# Viisilukk.net
KiCad netlist of a schematic drawn in EAGLE
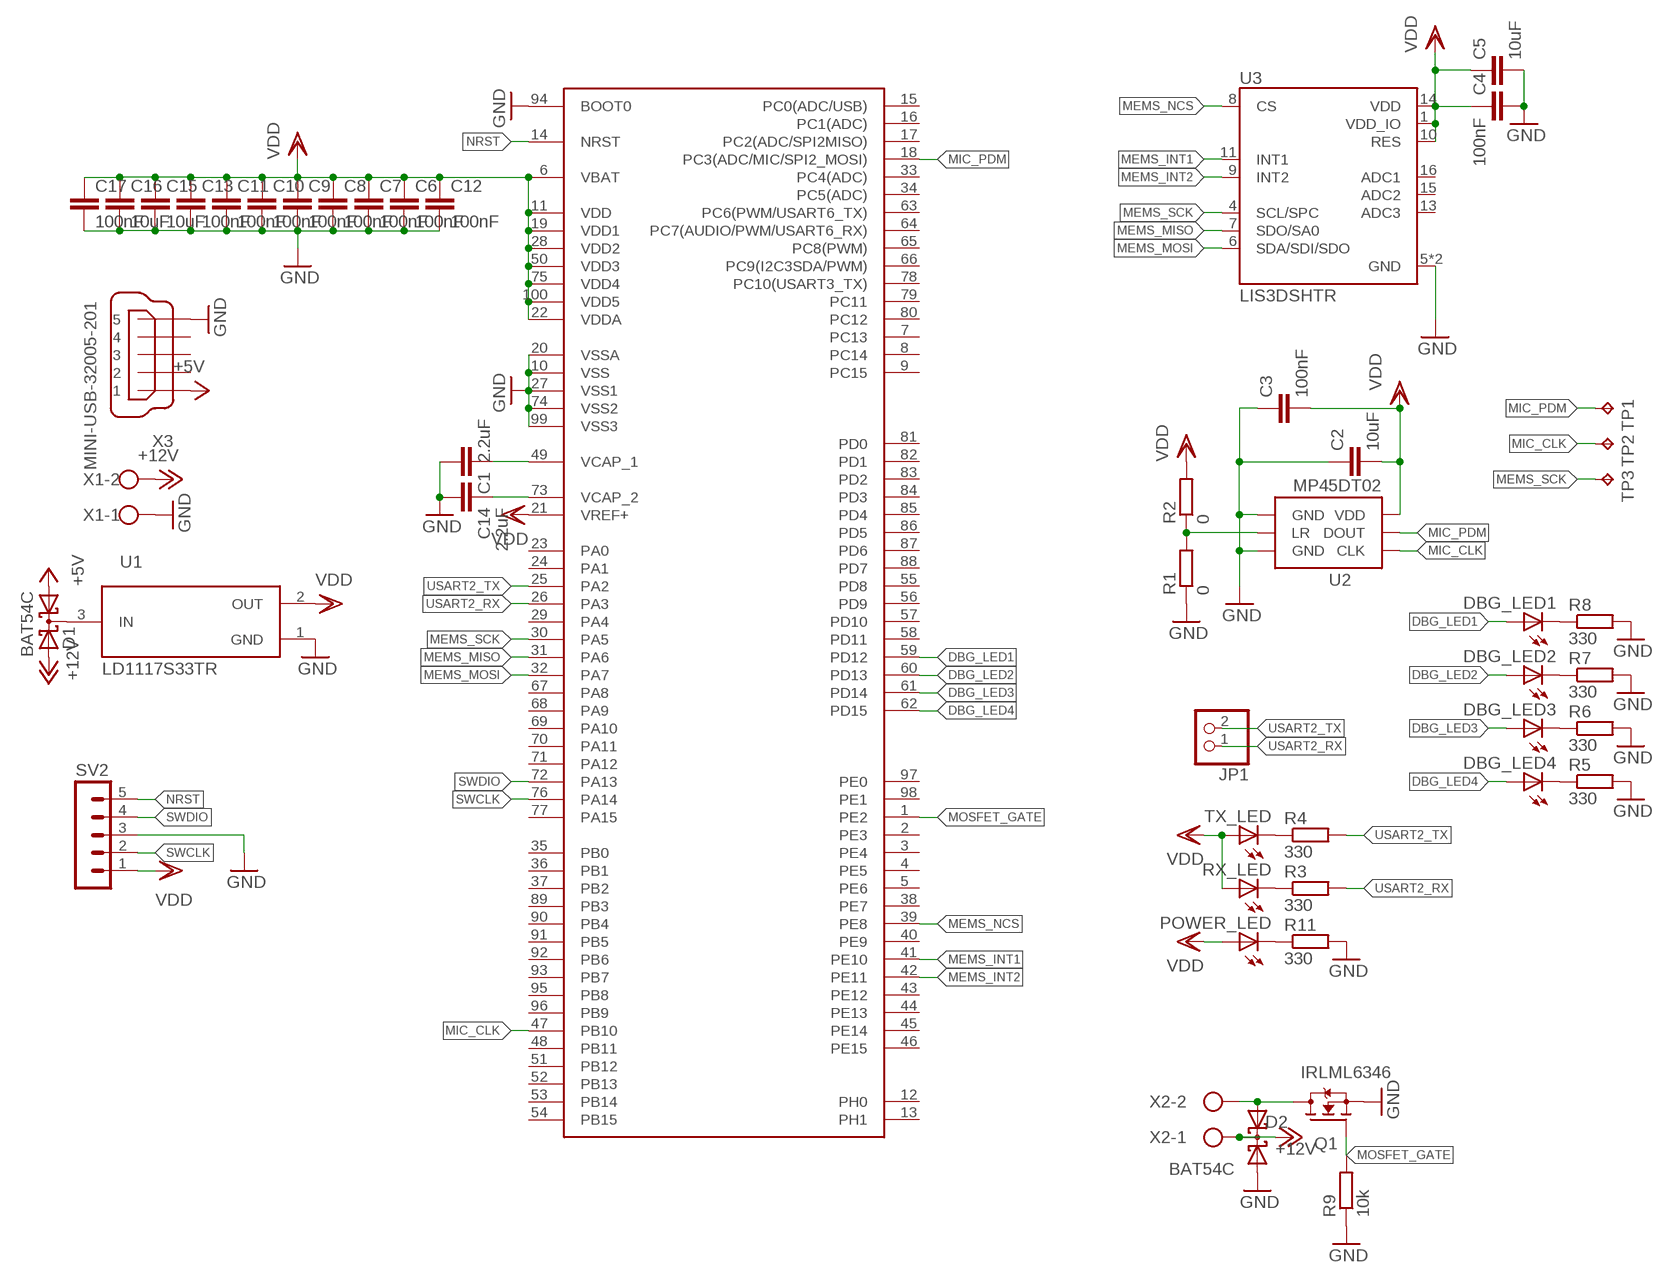
[diagram p0: schematic, sheet 1]

(export (version "E")
  (design (tool "Eeschema 10.0.6"))
  (components
    (comp (ref "C1")
      (value "2.2uF")
      (footprint "eagle-import:C0603")
      (libsource (lib "eagle-import") (part "C-EUC0603"))
    )
    (comp (ref "C2")
      (value "10uF")
      (footprint "eagle-import:C0805")
      (libsource (lib "eagle-import") (part "C-EUC0805"))
    )
    (comp (ref "C3")
      (value "100nF")
      (footprint "eagle-import:C0603")
      (libsource (lib "eagle-import") (part "C-EUC0603"))
    )
    (comp (ref "C4")
      (value "100nF")
      (footprint "eagle-import:C0603")
      (libsource (lib "eagle-import") (part "C-EUC0603"))
    )
    (comp (ref "C5")
      (value "10uF")
      (footprint "eagle-import:C0805")
      (libsource (lib "eagle-import") (part "C-EUC0805"))
    )
    (comp (ref "C6")
      (value "100nF")
      (footprint "eagle-import:C0603")
      (libsource (lib "eagle-import") (part "C-EUC0603"))
    )
    (comp (ref "C7")
      (value "100nF")
      (footprint "eagle-import:C0603")
      (libsource (lib "eagle-import") (part "C-EUC0603"))
    )
    (comp (ref "C8")
      (value "100nF")
      (footprint "eagle-import:C0603")
      (libsource (lib "eagle-import") (part "C-EUC0603"))
    )
    (comp (ref "C9")
      (value "100nF")
      (footprint "eagle-import:C0603")
      (libsource (lib "eagle-import") (part "C-EUC0603"))
    )
    (comp (ref "C10")
      (value "100nF")
      (footprint "eagle-import:C0603")
      (libsource (lib "eagle-import") (part "C-EUC0603"))
    )
    (comp (ref "C11")
      (value "100nF")
      (footprint "eagle-import:C0603")
      (libsource (lib "eagle-import") (part "C-EUC0603"))
    )
    (comp (ref "C12")
      (value "100nF")
      (footprint "eagle-import:C0603")
      (libsource (lib "eagle-import") (part "C-EUC0603"))
    )
    (comp (ref "C13")
      (value "100nF")
      (footprint "eagle-import:C0603")
      (libsource (lib "eagle-import") (part "C-EUC0603"))
    )
    (comp (ref "C14")
      (value "2.2uF")
      (footprint "eagle-import:C0603")
      (libsource (lib "eagle-import") (part "C-EUC0603"))
    )
    (comp (ref "C15")
      (value "10uF")
      (footprint "eagle-import:C0805")
      (libsource (lib "eagle-import") (part "C-EUC0805"))
    )
    (comp (ref "C16")
      (value "10uF")
      (footprint "eagle-import:C0805")
      (libsource (lib "eagle-import") (part "C-EUC0805"))
    )
    (comp (ref "C17")
      (value "100nF")
      (footprint "eagle-import:C0603")
      (libsource (lib "eagle-import") (part "C-EUC0603"))
    )
    (comp (ref "D1")
      (value "BAT54C")
      (footprint "eagle-import:SOT23")
      (libsource (lib "eagle-import") (part "BAT54C"))
    )
    (comp (ref "D2")
      (value "BAT54C")
      (footprint "eagle-import:SOT23")
      (libsource (lib "eagle-import") (part "BAT54C"))
    )
    (comp (ref "DBG_LED1")
      (value "LEDCHIP-LED0603")
      (footprint "eagle-import:CHIP-LED0603")
      (libsource (lib "eagle-import") (part "LEDCHIP-LED0603"))
    )
    (comp (ref "DBG_LED2")
      (value "LEDCHIP-LED0603")
      (footprint "eagle-import:CHIP-LED0603")
      (libsource (lib "eagle-import") (part "LEDCHIP-LED0603"))
    )
    (comp (ref "DBG_LED3")
      (value "LEDCHIP-LED0603")
      (footprint "eagle-import:CHIP-LED0603")
      (libsource (lib "eagle-import") (part "LEDCHIP-LED0603"))
    )
    (comp (ref "DBG_LED4")
      (value "LEDCHIP-LED0603")
      (footprint "eagle-import:CHIP-LED0603")
      (libsource (lib "eagle-import") (part "LEDCHIP-LED0603"))
    )
    (comp (ref "JP1")
      (value "PINHD-1X2")
      (footprint "eagle-import:1X02")
      (libsource (lib "eagle-import") (part "PINHD-1X2"))
    )
    (comp (ref "POWER_LED")
      (value "LEDCHIP-LED0603")
      (footprint "eagle-import:CHIP-LED0603")
      (libsource (lib "eagle-import") (part "LEDCHIP-LED0603"))
    )
    (comp (ref "Q1")
      (value "IRLML6346")
      (footprint "eagle-import:SOT23")
      (fields (field (name "MF") "Fairchild") (field (name "MPN") "BSS138"))
      (libsource (lib "eagle-import") (part "IRLML6346"))
    )
    (comp (ref "R1")
      (value "0")
      (footprint "eagle-import:R0603")
      (libsource (lib "eagle-import") (part "R-EU_R0603"))
    )
    (comp (ref "R2")
      (value "0")
      (footprint "eagle-import:R0603")
      (libsource (lib "eagle-import") (part "R-EU_R0603"))
    )
    (comp (ref "R3")
      (value "330")
      (footprint "eagle-import:R0603")
      (libsource (lib "eagle-import") (part "R-EU_R0603"))
    )
    (comp (ref "R4")
      (value "330")
      (footprint "eagle-import:R0603")
      (libsource (lib "eagle-import") (part "R-EU_R0603"))
    )
    (comp (ref "R5")
      (value "330")
      (footprint "eagle-import:R0603")
      (libsource (lib "eagle-import") (part "R-EU_R0603"))
    )
    (comp (ref "R6")
      (value "330")
      (footprint "eagle-import:R0603")
      (libsource (lib "eagle-import") (part "R-EU_R0603"))
    )
    (comp (ref "R7")
      (value "330")
      (footprint "eagle-import:R0603")
      (libsource (lib "eagle-import") (part "R-EU_R0603"))
    )
    (comp (ref "R8")
      (value "330")
      (footprint "eagle-import:R0603")
      (libsource (lib "eagle-import") (part "R-EU_R0603"))
    )
    (comp (ref "R9")
      (value "10k")
      (footprint "eagle-import:R0603")
      (libsource (lib "eagle-import") (part "R-EU_R0603"))
    )
    (comp (ref "R11")
      (value "330")
      (footprint "eagle-import:R0603")
      (libsource (lib "eagle-import") (part "R-EU_R0603"))
    )
    (comp (ref "RX_LED")
      (value "LEDCHIP-LED0603")
      (footprint "eagle-import:CHIP-LED0603")
      (libsource (lib "eagle-import") (part "LEDCHIP-LED0603"))
    )
    (comp (ref "SV2")
      (value "MA05-1")
      (footprint "eagle-import:MA05-1")
      (libsource (lib "eagle-import") (part "MA05-1"))
    )
    (comp (ref "TP1")
      (value "TPB2,54")
      (footprint "eagle-import:B2,54")
      (libsource (lib "eagle-import") (part "TPB2,54"))
    )
    (comp (ref "TP2")
      (value "TPB2,54")
      (footprint "eagle-import:B2,54")
      (libsource (lib "eagle-import") (part "TPB2,54"))
    )
    (comp (ref "TP3")
      (value "TPB2,54")
      (footprint "eagle-import:B2,54")
      (libsource (lib "eagle-import") (part "TPB2,54"))
    )
    (comp (ref "TX_LED")
      (value "LEDCHIP-LED0603")
      (footprint "eagle-import:CHIP-LED0603")
      (libsource (lib "eagle-import") (part "LEDCHIP-LED0603"))
    )
    (comp (ref "U$1")
      (value "STM32F407STM32D40X")
      (footprint "eagle-import:LQFP100")
      (libsource (lib "eagle-import") (part "STM32F407STM32D40X"))
    )
    (comp (ref "U1")
      (value "LD1117S33TR")
      (footprint "eagle-import:SOT230P700X180-4N")
      (fields (field (name "MF") "STMicroelectronics"))
      (libsource (lib "eagle-import") (part "LD1117S33TR"))
    )
    (comp (ref "U2")
      (value "MP45DT02")
      (footprint "eagle-import:ST_HLGA6")
      (fields (field (name "MF") "STMicroelectronics"))
      (libsource (lib "eagle-import") (part "MP45DT02"))
    )
    (comp (ref "U3")
      (value "LIS3DSHTR")
      (footprint "eagle-import:LGA16R50P5X3_300X300X100N")
      (fields (field (name "MF") "STMicroelectronics"))
      (libsource (lib "eagle-import") (part "LIS3DSHTR"))
    )
    (comp (ref "X1")
      (value "W237-102")
      (footprint "eagle-import:W237-102")
      (fields (field (name "MPN") "237-102"))
      (libsource (lib "eagle-import") (part "W237-102"))
    )
    (comp (ref "X2")
      (value "W237-102")
      (footprint "eagle-import:W237-102")
      (fields (field (name "MPN") "237-102"))
      (libsource (lib "eagle-import") (part "W237-102"))
    )
    (comp (ref "X3")
      (value "MINI-USB-32005-201")
      (footprint "eagle-import:32005-201")
      (libsource (lib "eagle-import") (part "MINI-USB-32005-201"))
    )
  )
  (nets
    (net (code "1") (name "+5V") (class "Default")
      (node (ref "D1") (pin "1") (pinfunction "A1_1") (pintype "passive"))
      (node (ref "X3") (pin "1") (pinfunction "1_1") (pintype "passive"))
    )
    (net (code "2") (name "+12V") (class "Default")
      (node (ref "D1") (pin "2") (pinfunction "A2_2") (pintype "passive"))
      (node (ref "D2") (pin "3") (pinfunction "CC_3") (pintype "passive"))
      (node (ref "X1") (pin "2") (pinfunction "KL_2") (pintype "passive"))
      (node (ref "X2") (pin "1") (pinfunction "KL_1") (pintype "passive"))
    )
    (net (code "3") (name "DBG_LED1") (class "Default")
      (node (ref "DBG_LED1") (pin "A") (pinfunction "A_A") (pintype "passive"))
      (node (ref "U$1") (pin "59") (pinfunction "PD12_59") (pintype "bidirectional"))
    )
    (net (code "4") (name "DBG_LED2") (class "Default")
      (node (ref "DBG_LED2") (pin "A") (pinfunction "A_A") (pintype "passive"))
      (node (ref "U$1") (pin "60") (pinfunction "PD13_60") (pintype "bidirectional"))
    )
    (net (code "5") (name "DBG_LED3") (class "Default")
      (node (ref "DBG_LED3") (pin "A") (pinfunction "A_A") (pintype "passive"))
      (node (ref "U$1") (pin "61") (pinfunction "PD14_61") (pintype "bidirectional"))
    )
    (net (code "6") (name "DBG_LED4") (class "Default")
      (node (ref "DBG_LED4") (pin "A") (pinfunction "A_A") (pintype "passive"))
      (node (ref "U$1") (pin "62") (pinfunction "PD15_62") (pintype "bidirectional"))
    )
    (net (code "7") (name "GND") (class "Default")
      (node (ref "C1") (pin "2") (pinfunction "2_2") (pintype "passive"))
      (node (ref "C10") (pin "2") (pinfunction "2_2") (pintype "passive"))
      (node (ref "C11") (pin "2") (pinfunction "2_2") (pintype "passive"))
      (node (ref "C12") (pin "2") (pinfunction "2_2") (pintype "passive"))
      (node (ref "C13") (pin "2") (pinfunction "2_2") (pintype "passive"))
      (node (ref "C14") (pin "2") (pinfunction "2_2") (pintype "passive"))
      (node (ref "C15") (pin "2") (pinfunction "2_2") (pintype "passive"))
      (node (ref "C16") (pin "2") (pinfunction "2_2") (pintype "passive"))
      (node (ref "C17") (pin "2") (pinfunction "2_2") (pintype "passive"))
      (node (ref "C2") (pin "1") (pinfunction "1_1") (pintype "passive"))
      (node (ref "C3") (pin "1") (pinfunction "1_1") (pintype "passive"))
      (node (ref "C4") (pin "2") (pinfunction "2_2") (pintype "passive"))
      (node (ref "C5") (pin "2") (pinfunction "2_2") (pintype "passive"))
      (node (ref "C6") (pin "2") (pinfunction "2_2") (pintype "passive"))
      (node (ref "C7") (pin "2") (pinfunction "2_2") (pintype "passive"))
      (node (ref "C8") (pin "2") (pinfunction "2_2") (pintype "passive"))
      (node (ref "C9") (pin "2") (pinfunction "2_2") (pintype "passive"))
      (node (ref "D2") (pin "1") (pinfunction "A1_1") (pintype "passive"))
      (node (ref "Q1") (pin "2") (pinfunction "S_2") (pintype "passive"))
      (node (ref "R1") (pin "1") (pinfunction "1_1") (pintype "passive"))
      (node (ref "R11") (pin "2") (pinfunction "2_2") (pintype "passive"))
      (node (ref "R5") (pin "2") (pinfunction "2_2") (pintype "passive"))
      (node (ref "R6") (pin "2") (pinfunction "2_2") (pintype "passive"))
      (node (ref "R7") (pin "2") (pinfunction "2_2") (pintype "passive"))
      (node (ref "R8") (pin "2") (pinfunction "2_2") (pintype "passive"))
      (node (ref "R9") (pin "1") (pinfunction "1_1") (pintype "passive"))
      (node (ref "SV2") (pin "3") (pinfunction "3_3") (pintype "passive"))
      (node (ref "U$1") (pin "10") (pinfunction "VSS_10") (pintype "bidirectional"))
      (node (ref "U$1") (pin "20") (pinfunction "VSSA_20") (pintype "bidirectional"))
      (node (ref "U$1") (pin "27") (pinfunction "VSS1_27") (pintype "bidirectional"))
      (node (ref "U$1") (pin "74") (pinfunction "VSS2_74") (pintype "bidirectional"))
      (node (ref "U$1") (pin "94") (pinfunction "BOOT0_94") (pintype "bidirectional"))
      (node (ref "U$1") (pin "99") (pinfunction "VSS3_99") (pintype "bidirectional"))
      (node (ref "U1") (pin "1") (pinfunction "GND_1") (pintype "power_in"))
      (node (ref "U2") (pin "1") (pinfunction "GND_1") (pintype "bidirectional"))
      (node (ref "U2") (pin "3") (pinfunction "GND_3") (pintype "bidirectional"))
      (node (ref "U3") (pin "12") (pinfunction "GND_12") (pintype "power_in"))
      (node (ref "U3") (pin "5") (pinfunction "GND_5") (pintype "power_in"))
      (node (ref "X1") (pin "1") (pinfunction "KL_1") (pintype "passive"))
      (node (ref "X3") (pin "5") (pinfunction "5_5") (pintype "passive"))
    )
    (net (code "8") (name "MEMS_INT1") (class "Default")
      (node (ref "U$1") (pin "41") (pinfunction "PE10_41") (pintype "bidirectional"))
      (node (ref "U3") (pin "11") (pinfunction "INT1_11") (pintype "input"))
    )
    (net (code "9") (name "MEMS_INT2") (class "Default")
      (node (ref "U$1") (pin "42") (pinfunction "PE11_42") (pintype "bidirectional"))
      (node (ref "U3") (pin "9") (pinfunction "INT2_9") (pintype "input"))
    )
    (net (code "10") (name "MEMS_MISO") (class "Default")
      (node (ref "U$1") (pin "31") (pinfunction "PA6_31") (pintype "bidirectional"))
      (node (ref "U3") (pin "7") (pinfunction "SDO/SA0_7") (pintype "output"))
    )
    (net (code "11") (name "MEMS_MOSI") (class "Default")
      (node (ref "U$1") (pin "32") (pinfunction "PA7_32") (pintype "bidirectional"))
      (node (ref "U3") (pin "6") (pinfunction "SDA/SDI/SDO_6") (pintype "bidirectional"))
    )
    (net (code "12") (name "MEMS_NCS") (class "Default")
      (node (ref "U$1") (pin "39") (pinfunction "PE8_39") (pintype "bidirectional"))
      (node (ref "U3") (pin "8") (pinfunction "CS_8") (pintype "input"))
    )
    (net (code "13") (name "MEMS_SCK") (class "Default")
      (node (ref "TP3") (pin "TP") (pinfunction "TP_TP") (pintype "input"))
      (node (ref "U$1") (pin "30") (pinfunction "PA5_30") (pintype "bidirectional"))
      (node (ref "U3") (pin "4") (pinfunction "SCL/SPC_4") (pintype "input"))
    )
    (net (code "14") (name "MIC_CLK") (class "Default")
      (node (ref "TP2") (pin "TP") (pinfunction "TP_TP") (pintype "input"))
      (node (ref "U$1") (pin "47") (pinfunction "PB10_47") (pintype "bidirectional"))
      (node (ref "U2") (pin "4") (pinfunction "CLK_4") (pintype "bidirectional"))
    )
    (net (code "15") (name "MIC_PDM") (class "Default")
      (node (ref "TP1") (pin "TP") (pinfunction "TP_TP") (pintype "input"))
      (node (ref "U$1") (pin "18") (pinfunction "PC3(ADC/MIC/SPI2_MOSI)_18") (pintype "bidirectional"))
      (node (ref "U2") (pin "5") (pinfunction "DOUT_5") (pintype "bidirectional"))
    )
    (net (code "16") (name "MOSFET_GATE") (class "Default")
      (node (ref "Q1") (pin "1") (pinfunction "G_1") (pintype "passive"))
      (node (ref "R9") (pin "2") (pinfunction "2_2") (pintype "passive"))
      (node (ref "U$1") (pin "1") (pinfunction "PE2_1") (pintype "bidirectional"))
    )
    (net (code "17") (name "NRST") (class "Default")
      (node (ref "SV2") (pin "5") (pinfunction "5_5") (pintype "passive"))
      (node (ref "U$1") (pin "14") (pinfunction "NRST_14") (pintype "bidirectional"))
    )
    (net (code "18") (name "Net-(D1-CC)") (class "Default")
      (node (ref "D1") (pin "3") (pinfunction "CC_3") (pintype "passive"))
      (node (ref "U1") (pin "3") (pinfunction "IN_3") (pintype "input"))
    )
    (net (code "19") (name "Net-(D2-A2)") (class "Default")
      (node (ref "D2") (pin "2") (pinfunction "A2_2") (pintype "passive"))
      (node (ref "Q1") (pin "3") (pinfunction "D_3") (pintype "passive"))
      (node (ref "X2") (pin "2") (pinfunction "KL_2") (pintype "passive"))
    )
    (net (code "20") (name "Net-(DBG_LED1-PadC)") (class "Default")
      (node (ref "DBG_LED1") (pin "C") (pinfunction "C_C") (pintype "passive"))
      (node (ref "R8") (pin "1") (pinfunction "1_1") (pintype "passive"))
    )
    (net (code "21") (name "Net-(DBG_LED2-PadC)") (class "Default")
      (node (ref "DBG_LED2") (pin "C") (pinfunction "C_C") (pintype "passive"))
      (node (ref "R7") (pin "1") (pinfunction "1_1") (pintype "passive"))
    )
    (net (code "22") (name "Net-(DBG_LED3-PadC)") (class "Default")
      (node (ref "DBG_LED3") (pin "C") (pinfunction "C_C") (pintype "passive"))
      (node (ref "R6") (pin "1") (pinfunction "1_1") (pintype "passive"))
    )
    (net (code "23") (name "Net-(DBG_LED4-PadC)") (class "Default")
      (node (ref "DBG_LED4") (pin "C") (pinfunction "C_C") (pintype "passive"))
      (node (ref "R5") (pin "1") (pinfunction "1_1") (pintype "passive"))
    )
    (net (code "24") (name "Net-(POWER_LED-PadC)") (class "Default")
      (node (ref "POWER_LED") (pin "C") (pinfunction "C_C") (pintype "passive"))
      (node (ref "R11") (pin "1") (pinfunction "1_1") (pintype "passive"))
    )
    (net (code "25") (name "Net-(R3-Pad1)") (class "Default")
      (node (ref "R3") (pin "1") (pinfunction "1_1") (pintype "passive"))
      (node (ref "RX_LED") (pin "C") (pinfunction "C_C") (pintype "passive"))
    )
    (net (code "26") (name "Net-(R4-Pad1)") (class "Default")
      (node (ref "R4") (pin "1") (pinfunction "1_1") (pintype "passive"))
      (node (ref "TX_LED") (pin "C") (pinfunction "C_C") (pintype "passive"))
    )
    (net (code "27") (name "Net-(U$1-VCAP_1)") (class "Default")
      (node (ref "C1") (pin "1") (pinfunction "1_1") (pintype "passive"))
      (node (ref "U$1") (pin "49") (pinfunction "VCAP_1_49") (pintype "bidirectional"))
    )
    (net (code "28") (name "Net-(U$1-VCAP_2)") (class "Default")
      (node (ref "C14") (pin "1") (pinfunction "1_1") (pintype "passive"))
      (node (ref "U$1") (pin "73") (pinfunction "VCAP_2_73") (pintype "bidirectional"))
    )
    (net (code "29") (name "Net-(U2-LR)") (class "Default")
      (node (ref "R1") (pin "2") (pinfunction "2_2") (pintype "passive"))
      (node (ref "R2") (pin "1") (pinfunction "1_1") (pintype "passive"))
      (node (ref "U2") (pin "2") (pinfunction "LR_2") (pintype "bidirectional"))
    )
    (net (code "30") (name "SWCLK") (class "Default")
      (node (ref "SV2") (pin "2") (pinfunction "2_2") (pintype "passive"))
      (node (ref "U$1") (pin "76") (pinfunction "PA14_76") (pintype "bidirectional"))
    )
    (net (code "31") (name "SWDIO") (class "Default")
      (node (ref "SV2") (pin "4") (pinfunction "4_4") (pintype "passive"))
      (node (ref "U$1") (pin "72") (pinfunction "PA13_72") (pintype "bidirectional"))
    )
    (net (code "32") (name "USART2_RX") (class "Default")
      (node (ref "JP1") (pin "1") (pinfunction "1_1") (pintype "passive"))
      (node (ref "R3") (pin "2") (pinfunction "2_2") (pintype "passive"))
      (node (ref "U$1") (pin "26") (pinfunction "PA3_26") (pintype "bidirectional"))
    )
    (net (code "33") (name "USART2_TX") (class "Default")
      (node (ref "JP1") (pin "2") (pinfunction "2_2") (pintype "passive"))
      (node (ref "R4") (pin "2") (pinfunction "2_2") (pintype "passive"))
      (node (ref "U$1") (pin "25") (pinfunction "PA2_25") (pintype "bidirectional"))
    )
    (net (code "34") (name "VDD") (class "Default")
      (node (ref "C10") (pin "1") (pinfunction "1_1") (pintype "passive"))
      (node (ref "C11") (pin "1") (pinfunction "1_1") (pintype "passive"))
      (node (ref "C12") (pin "1") (pinfunction "1_1") (pintype "passive"))
      (node (ref "C13") (pin "1") (pinfunction "1_1") (pintype "passive"))
      (node (ref "C15") (pin "1") (pinfunction "1_1") (pintype "passive"))
      (node (ref "C16") (pin "1") (pinfunction "1_1") (pintype "passive"))
      (node (ref "C17") (pin "1") (pinfunction "1_1") (pintype "passive"))
      (node (ref "C2") (pin "2") (pinfunction "2_2") (pintype "passive"))
      (node (ref "C3") (pin "2") (pinfunction "2_2") (pintype "passive"))
      (node (ref "C4") (pin "1") (pinfunction "1_1") (pintype "passive"))
      (node (ref "C5") (pin "1") (pinfunction "1_1") (pintype "passive"))
      (node (ref "C6") (pin "1") (pinfunction "1_1") (pintype "passive"))
      (node (ref "C7") (pin "1") (pinfunction "1_1") (pintype "passive"))
      (node (ref "C8") (pin "1") (pinfunction "1_1") (pintype "passive"))
      (node (ref "C9") (pin "1") (pinfunction "1_1") (pintype "passive"))
      (node (ref "POWER_LED") (pin "A") (pinfunction "A_A") (pintype "passive"))
      (node (ref "R2") (pin "2") (pinfunction "2_2") (pintype "passive"))
      (node (ref "RX_LED") (pin "A") (pinfunction "A_A") (pintype "passive"))
      (node (ref "SV2") (pin "1") (pinfunction "1_1") (pintype "passive"))
      (node (ref "TX_LED") (pin "A") (pinfunction "A_A") (pintype "passive"))
      (node (ref "U$1") (pin "100") (pinfunction "VDD5_100") (pintype "bidirectional"))
      (node (ref "U$1") (pin "11") (pinfunction "VDD_11") (pintype "bidirectional"))
      (node (ref "U$1") (pin "19") (pinfunction "VDD1_19") (pintype "bidirectional"))
      (node (ref "U$1") (pin "21") (pinfunction "VREF+_21") (pintype "bidirectional"))
      (node (ref "U$1") (pin "22") (pinfunction "VDDA_22") (pintype "bidirectional"))
      (node (ref "U$1") (pin "28") (pinfunction "VDD2_28") (pintype "bidirectional"))
      (node (ref "U$1") (pin "50") (pinfunction "VDD3_50") (pintype "bidirectional"))
      (node (ref "U$1") (pin "6") (pinfunction "VBAT_6") (pintype "bidirectional"))
      (node (ref "U$1") (pin "75") (pinfunction "VDD4_75") (pintype "bidirectional"))
      (node (ref "U1") (pin "2") (pinfunction "OUT_2") (pintype "output"))
      (node (ref "U2") (pin "6") (pinfunction "VDD_6") (pintype "bidirectional"))
      (node (ref "U3") (pin "1") (pinfunction "VDD_IO_1") (pintype "power_in"))
      (node (ref "U3") (pin "10") (pinfunction "RES_10") (pintype "power_in"))
      (node (ref "U3") (pin "14") (pinfunction "VDD_14") (pintype "power_in"))
    )
    (net (code "35") (name "unconnected-(U$1-PA0-Pad23)") (class "Default")
      (node (ref "U$1") (pin "23") (pinfunction "PA0_23") (pintype "bidirectional"))
    )
    (net (code "36") (name "unconnected-(U$1-PA1-Pad24)") (class "Default")
      (node (ref "U$1") (pin "24") (pinfunction "PA1_24") (pintype "bidirectional"))
    )
    (net (code "37") (name "unconnected-(U$1-PA4-Pad29)") (class "Default")
      (node (ref "U$1") (pin "29") (pinfunction "PA4_29") (pintype "bidirectional"))
    )
    (net (code "38") (name "unconnected-(U$1-PA8-Pad67)") (class "Default")
      (node (ref "U$1") (pin "67") (pinfunction "PA8_67") (pintype "bidirectional"))
    )
    (net (code "39") (name "unconnected-(U$1-PA9-Pad68)") (class "Default")
      (node (ref "U$1") (pin "68") (pinfunction "PA9_68") (pintype "bidirectional"))
    )
    (net (code "40") (name "unconnected-(U$1-PA10-Pad69)") (class "Default")
      (node (ref "U$1") (pin "69") (pinfunction "PA10_69") (pintype "bidirectional"))
    )
    (net (code "41") (name "unconnected-(U$1-PA11-Pad70)") (class "Default")
      (node (ref "U$1") (pin "70") (pinfunction "PA11_70") (pintype "bidirectional"))
    )
    (net (code "42") (name "unconnected-(U$1-PA12-Pad71)") (class "Default")
      (node (ref "U$1") (pin "71") (pinfunction "PA12_71") (pintype "bidirectional"))
    )
    (net (code "43") (name "unconnected-(U$1-PA15-Pad77)") (class "Default")
      (node (ref "U$1") (pin "77") (pinfunction "PA15_77") (pintype "bidirectional"))
    )
    (net (code "44") (name "unconnected-(U$1-PB0-Pad35)") (class "Default")
      (node (ref "U$1") (pin "35") (pinfunction "PB0_35") (pintype "bidirectional"))
    )
    (net (code "45") (name "unconnected-(U$1-PB1-Pad36)") (class "Default")
      (node (ref "U$1") (pin "36") (pinfunction "PB1_36") (pintype "bidirectional"))
    )
    (net (code "46") (name "unconnected-(U$1-PB2-Pad37)") (class "Default")
      (node (ref "U$1") (pin "37") (pinfunction "PB2_37") (pintype "bidirectional"))
    )
    (net (code "47") (name "unconnected-(U$1-PB3-Pad89)") (class "Default")
      (node (ref "U$1") (pin "89") (pinfunction "PB3_89") (pintype "bidirectional"))
    )
    (net (code "48") (name "unconnected-(U$1-PB4-Pad90)") (class "Default")
      (node (ref "U$1") (pin "90") (pinfunction "PB4_90") (pintype "bidirectional"))
    )
    (net (code "49") (name "unconnected-(U$1-PB5-Pad91)") (class "Default")
      (node (ref "U$1") (pin "91") (pinfunction "PB5_91") (pintype "bidirectional"))
    )
    (net (code "50") (name "unconnected-(U$1-PB6-Pad92)") (class "Default")
      (node (ref "U$1") (pin "92") (pinfunction "PB6_92") (pintype "bidirectional"))
    )
    (net (code "51") (name "unconnected-(U$1-PB7-Pad93)") (class "Default")
      (node (ref "U$1") (pin "93") (pinfunction "PB7_93") (pintype "bidirectional"))
    )
    (net (code "52") (name "unconnected-(U$1-PB8-Pad95)") (class "Default")
      (node (ref "U$1") (pin "95") (pinfunction "PB8_95") (pintype "bidirectional"))
    )
    (net (code "53") (name "unconnected-(U$1-PB9-Pad96)") (class "Default")
      (node (ref "U$1") (pin "96") (pinfunction "PB9_96") (pintype "bidirectional"))
    )
    (net (code "54") (name "unconnected-(U$1-PB11-Pad48)") (class "Default")
      (node (ref "U$1") (pin "48") (pinfunction "PB11_48") (pintype "bidirectional"))
    )
    (net (code "55") (name "unconnected-(U$1-PB12-Pad51)") (class "Default")
      (node (ref "U$1") (pin "51") (pinfunction "PB12_51") (pintype "bidirectional"))
    )
    (net (code "56") (name "unconnected-(U$1-PB13-Pad52)") (class "Default")
      (node (ref "U$1") (pin "52") (pinfunction "PB13_52") (pintype "bidirectional"))
    )
    (net (code "57") (name "unconnected-(U$1-PB14-Pad53)") (class "Default")
      (node (ref "U$1") (pin "53") (pinfunction "PB14_53") (pintype "bidirectional"))
    )
    (net (code "58") (name "unconnected-(U$1-PB15-Pad54)") (class "Default")
      (node (ref "U$1") (pin "54") (pinfunction "PB15_54") (pintype "bidirectional"))
    )
    (net (code "59") (name "unconnected-(U$1-PC0(ADC{slash}USB)-Pad15)") (class "Default")
      (node (ref "U$1") (pin "15") (pinfunction "PC0(ADC/USB)_15") (pintype "bidirectional"))
    )
    (net (code "60") (name "unconnected-(U$1-PC1(ADC)-Pad16)") (class "Default")
      (node (ref "U$1") (pin "16") (pinfunction "PC1(ADC)_16") (pintype "bidirectional"))
    )
    (net (code "61") (name "unconnected-(U$1-PC2(ADC{slash}SPI2MISO)-Pad17)") (class "Default")
      (node (ref "U$1") (pin "17") (pinfunction "PC2(ADC/SPI2MISO)_17") (pintype "bidirectional"))
    )
    (net (code "62") (name "unconnected-(U$1-PC4(ADC)-Pad33)") (class "Default")
      (node (ref "U$1") (pin "33") (pinfunction "PC4(ADC)_33") (pintype "bidirectional"))
    )
    (net (code "63") (name "unconnected-(U$1-PC5(ADC)-Pad34)") (class "Default")
      (node (ref "U$1") (pin "34") (pinfunction "PC5(ADC)_34") (pintype "bidirectional"))
    )
    (net (code "64") (name "unconnected-(U$1-PC6(PWM{slash}USART6_TX)-Pad63)") (class "Default")
      (node (ref "U$1") (pin "63") (pinfunction "PC6(PWM/USART6_TX)_63") (pintype "bidirectional"))
    )
    (net (code "65") (name "unconnected-(U$1-PC7(AUDIO{slash}PWM{slash}USART6_RX)-Pad64)") (class "Default")
      (node (ref "U$1") (pin "64") (pinfunction "PC7(AUDIO/PWM/USART6_RX)_64") (pintype "bidirectional"))
    )
    (net (code "66") (name "unconnected-(U$1-PC8(PWM)-Pad65)") (class "Default")
      (node (ref "U$1") (pin "65") (pinfunction "PC8(PWM)_65") (pintype "bidirectional"))
    )
    (net (code "67") (name "unconnected-(U$1-PC9(I2C3SDA{slash}PWM)-Pad66)") (class "Default")
      (node (ref "U$1") (pin "66") (pinfunction "PC9(I2C3SDA/PWM)_66") (pintype "bidirectional"))
    )
    (net (code "68") (name "unconnected-(U$1-PC10(USART3_TX)-Pad78)") (class "Default")
      (node (ref "U$1") (pin "78") (pinfunction "PC10(USART3_TX)_78") (pintype "bidirectional"))
    )
    (net (code "69") (name "unconnected-(U$1-PC11-Pad79)") (class "Default")
      (node (ref "U$1") (pin "79") (pinfunction "PC11_79") (pintype "bidirectional"))
    )
    (net (code "70") (name "unconnected-(U$1-PC12-Pad80)") (class "Default")
      (node (ref "U$1") (pin "80") (pinfunction "PC12_80") (pintype "bidirectional"))
    )
    (net (code "71") (name "unconnected-(U$1-PC13-Pad7)") (class "Default")
      (node (ref "U$1") (pin "7") (pinfunction "PC13_7") (pintype "bidirectional"))
    )
    (net (code "72") (name "unconnected-(U$1-PC14-Pad8)") (class "Default")
      (node (ref "U$1") (pin "8") (pinfunction "PC14_8") (pintype "bidirectional"))
    )
    (net (code "73") (name "unconnected-(U$1-PC15-Pad9)") (class "Default")
      (node (ref "U$1") (pin "9") (pinfunction "PC15_9") (pintype "bidirectional"))
    )
    (net (code "74") (name "unconnected-(U$1-PD0-Pad81)") (class "Default")
      (node (ref "U$1") (pin "81") (pinfunction "PD0_81") (pintype "bidirectional"))
    )
    (net (code "75") (name "unconnected-(U$1-PD1-Pad82)") (class "Default")
      (node (ref "U$1") (pin "82") (pinfunction "PD1_82") (pintype "bidirectional"))
    )
    (net (code "76") (name "unconnected-(U$1-PD2-Pad83)") (class "Default")
      (node (ref "U$1") (pin "83") (pinfunction "PD2_83") (pintype "bidirectional"))
    )
    (net (code "77") (name "unconnected-(U$1-PD3-Pad84)") (class "Default")
      (node (ref "U$1") (pin "84") (pinfunction "PD3_84") (pintype "bidirectional"))
    )
    (net (code "78") (name "unconnected-(U$1-PD4-Pad85)") (class "Default")
      (node (ref "U$1") (pin "85") (pinfunction "PD4_85") (pintype "bidirectional"))
    )
    (net (code "79") (name "unconnected-(U$1-PD5-Pad86)") (class "Default")
      (node (ref "U$1") (pin "86") (pinfunction "PD5_86") (pintype "bidirectional"))
    )
    (net (code "80") (name "unconnected-(U$1-PD6-Pad87)") (class "Default")
      (node (ref "U$1") (pin "87") (pinfunction "PD6_87") (pintype "bidirectional"))
    )
    (net (code "81") (name "unconnected-(U$1-PD7-Pad88)") (class "Default")
      (node (ref "U$1") (pin "88") (pinfunction "PD7_88") (pintype "bidirectional"))
    )
    (net (code "82") (name "unconnected-(U$1-PD8-Pad55)") (class "Default")
      (node (ref "U$1") (pin "55") (pinfunction "PD8_55") (pintype "bidirectional"))
    )
    (net (code "83") (name "unconnected-(U$1-PD9-Pad56)") (class "Default")
      (node (ref "U$1") (pin "56") (pinfunction "PD9_56") (pintype "bidirectional"))
    )
    (net (code "84") (name "unconnected-(U$1-PD10-Pad57)") (class "Default")
      (node (ref "U$1") (pin "57") (pinfunction "PD10_57") (pintype "bidirectional"))
    )
    (net (code "85") (name "unconnected-(U$1-PD11-Pad58)") (class "Default")
      (node (ref "U$1") (pin "58") (pinfunction "PD11_58") (pintype "bidirectional"))
    )
    (net (code "86") (name "unconnected-(U$1-PE0-Pad97)") (class "Default")
      (node (ref "U$1") (pin "97") (pinfunction "PE0_97") (pintype "bidirectional"))
    )
    (net (code "87") (name "unconnected-(U$1-PE1-Pad98)") (class "Default")
      (node (ref "U$1") (pin "98") (pinfunction "PE1_98") (pintype "bidirectional"))
    )
    (net (code "88") (name "unconnected-(U$1-PE3-Pad2)") (class "Default")
      (node (ref "U$1") (pin "2") (pinfunction "PE3_2") (pintype "bidirectional"))
    )
    (net (code "89") (name "unconnected-(U$1-PE4-Pad3)") (class "Default")
      (node (ref "U$1") (pin "3") (pinfunction "PE4_3") (pintype "bidirectional"))
    )
    (net (code "90") (name "unconnected-(U$1-PE5-Pad4)") (class "Default")
      (node (ref "U$1") (pin "4") (pinfunction "PE5_4") (pintype "bidirectional"))
    )
    (net (code "91") (name "unconnected-(U$1-PE6-Pad5)") (class "Default")
      (node (ref "U$1") (pin "5") (pinfunction "PE6_5") (pintype "bidirectional"))
    )
    (net (code "92") (name "unconnected-(U$1-PE7-Pad38)") (class "Default")
      (node (ref "U$1") (pin "38") (pinfunction "PE7_38") (pintype "bidirectional"))
    )
    (net (code "93") (name "unconnected-(U$1-PE9-Pad40)") (class "Default")
      (node (ref "U$1") (pin "40") (pinfunction "PE9_40") (pintype "bidirectional"))
    )
    (net (code "94") (name "unconnected-(U$1-PE12-Pad43)") (class "Default")
      (node (ref "U$1") (pin "43") (pinfunction "PE12_43") (pintype "bidirectional"))
    )
    (net (code "95") (name "unconnected-(U$1-PE13-Pad44)") (class "Default")
      (node (ref "U$1") (pin "44") (pinfunction "PE13_44") (pintype "bidirectional"))
    )
    (net (code "96") (name "unconnected-(U$1-PE14-Pad45)") (class "Default")
      (node (ref "U$1") (pin "45") (pinfunction "PE14_45") (pintype "bidirectional"))
    )
    (net (code "97") (name "unconnected-(U$1-PE15-Pad46)") (class "Default")
      (node (ref "U$1") (pin "46") (pinfunction "PE15_46") (pintype "bidirectional"))
    )
    (net (code "98") (name "unconnected-(U$1-PH0-Pad12)") (class "Default")
      (node (ref "U$1") (pin "12") (pinfunction "PH0_12") (pintype "bidirectional"))
    )
    (net (code "99") (name "unconnected-(U$1-PH1-Pad13)") (class "Default")
      (node (ref "U$1") (pin "13") (pinfunction "PH1_13") (pintype "bidirectional"))
    )
    (net (code "100") (name "unconnected-(U3-ADC1-Pad16)") (class "Default")
      (node (ref "U3") (pin "16") (pinfunction "ADC1_16") (pintype "input"))
    )
    (net (code "101") (name "unconnected-(U3-ADC2-Pad15)") (class "Default")
      (node (ref "U3") (pin "15") (pinfunction "ADC2_15") (pintype "input"))
    )
    (net (code "102") (name "unconnected-(U3-ADC3-Pad13)") (class "Default")
      (node (ref "U3") (pin "13") (pinfunction "ADC3_13") (pintype "input"))
    )
    (net (code "103") (name "unconnected-(X3-Pad2)") (class "Default")
      (node (ref "X3") (pin "2") (pinfunction "2_2") (pintype "passive"))
    )
    (net (code "104") (name "unconnected-(X3-Pad3)") (class "Default")
      (node (ref "X3") (pin "3") (pinfunction "3_3") (pintype "passive"))
    )
    (net (code "105") (name "unconnected-(X3-Pad4)") (class "Default")
      (node (ref "X3") (pin "4") (pinfunction "4_4") (pintype "passive"))
    )
  )
)
